# RS485.net
KiCad netlist of a schematic drawn in Altium Designer
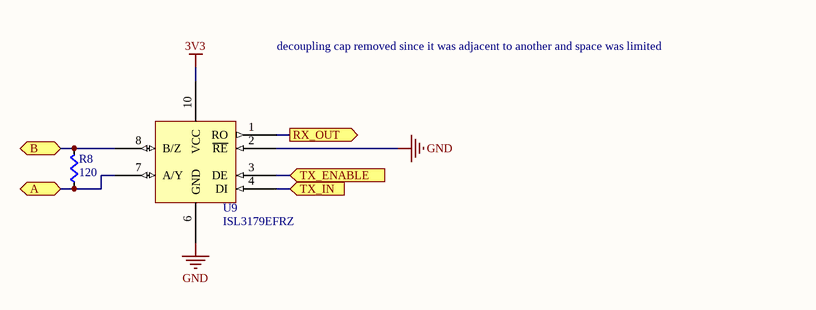
[diagram p0: RS485.SchDoc]

(export (version "E")
  (design (tool "Eeschema 10.0.6"))
  (components
    (comp (ref "R8")
      (value "120")
      (footprint "RES0603")
      (fields (field (name "Comment") "Res"))
      (libsource (lib "Passives") (part "Res"))
    )
    (comp (ref "U9")
      (value "ISL3179EFRZ")
      (footprint "ISL3179EFRZ_NO_VIAS")
      (description "TXRX ESD 3.3V RS-485/422 10-DFN")
      (libsource (lib "ICs") (part "ISL3179EFRZ"))
    )
  )
  (nets
    (net (code "1") (name "/A") (class "Default")
      (node (ref "R8") (pin "2") (pinfunction "B_2") (pintype "passive"))
      (node (ref "U9") (pin "7") (pinfunction "A/Y_7") (pintype "bidirectional"))
    )
    (net (code "2") (name "/B") (class "Default")
      (node (ref "R8") (pin "1") (pinfunction "A_1") (pintype "passive"))
      (node (ref "U9") (pin "8") (pinfunction "B/Z_8") (pintype "bidirectional"))
    )
    (net (code "3") (name "/RX_OUT") (class "Default")
      (node (ref "U9") (pin "1") (pinfunction "RO_1") (pintype "output"))
    )
    (net (code "4") (name "/TX_ENABLE") (class "Default")
      (node (ref "U9") (pin "3") (pinfunction "DE_3") (pintype "input"))
    )
    (net (code "5") (name "/TX_IN") (class "Default")
      (node (ref "U9") (pin "4") (pinfunction "DI_4") (pintype "input"))
    )
    (net (code "6") (name "3V3") (class "Default")
      (node (ref "U9") (pin "10") (pinfunction "VCC_10") (pintype "power_in"))
    )
    (net (code "7") (name "GND") (class "Default")
      (node (ref "U9") (pin "2") (pinfunction "~{RE}_2") (pintype "input"))
      (node (ref "U9") (pin "6") (pinfunction "GND_6") (pintype "power_in"))
    )
  )
)
